# Sheet1.net
KiCad netlist of a schematic drawn in Altium Designer
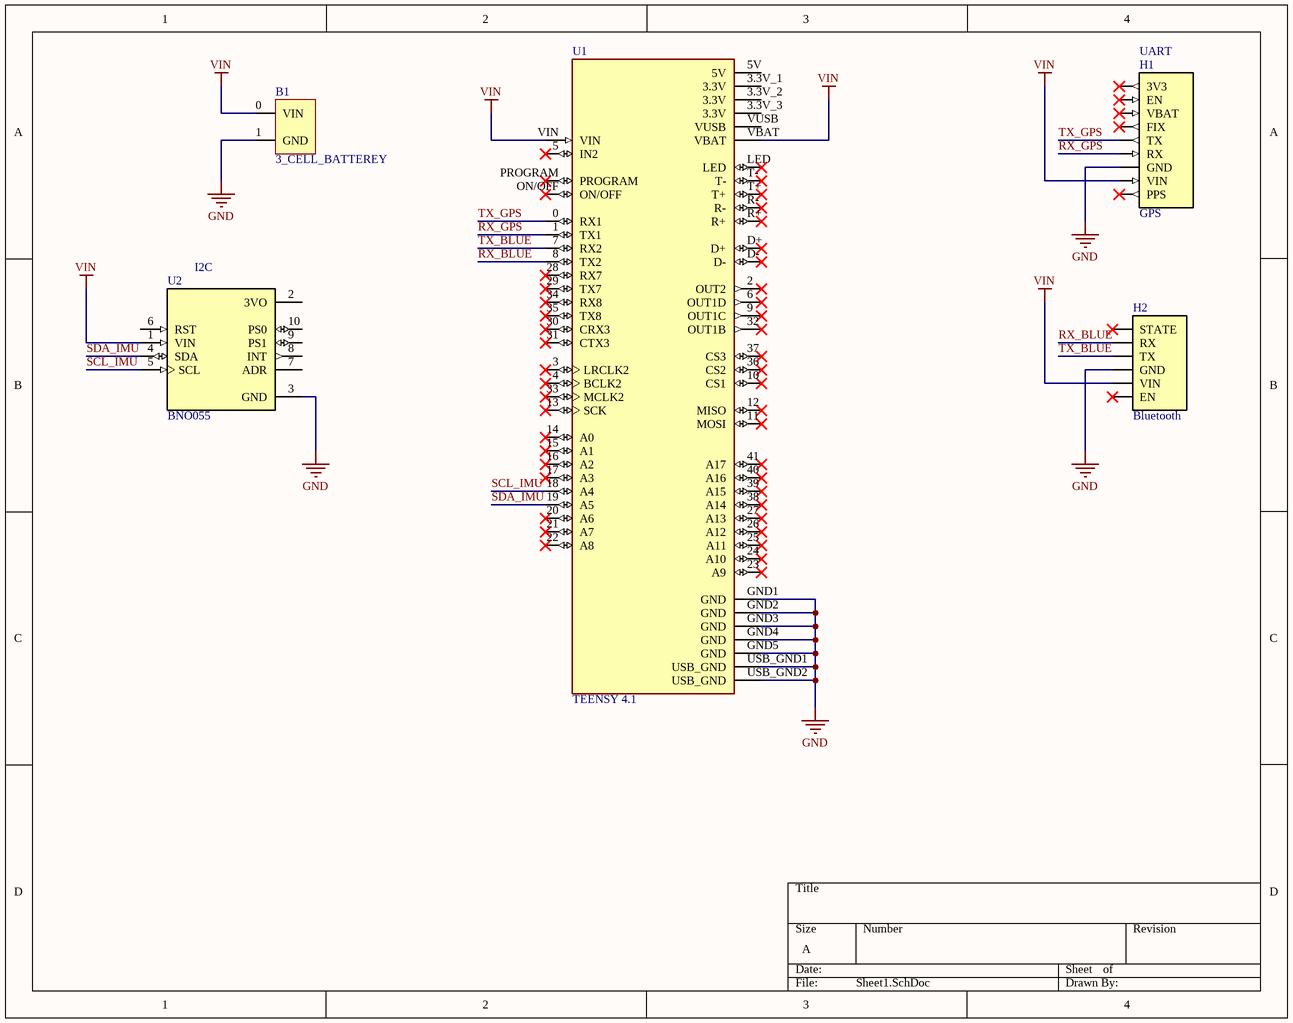
[diagram p0: Sheet1.SchDoc]

(export (version "E")
  (design (tool "Eeschema 10.0.6"))
  (components
    (comp (ref "B1")
      (value "3_CELL_BATTEREY")
      (footprint "3_CELL_BATTEREY")
      (libsource (lib "Schlib1") (part "3_CELL_BATTEREY"))
    )
    (comp (ref "H1") (value "GPS") (footprint "9X1_header") (libsource (lib "Schlib1") (part "9x1_header")))
    (comp (ref "H2")
      (value "Bluetooth")
      (footprint "61300611121")
      (libsource (lib "Schlib1") (part "Bluetooth"))
    )
    (comp (ref "U1")
      (value "TEENSY 4.1")
      (footprint "MODULE_DEV-16771")
      (description "RT1062 Teensy 4.1 series ARM® Cortex®-M7 MPU Embedded Evaluation Board")
      (fields (field (name "MF") "SparkFun Electronics") (field (name "MP") "DEV-16771"))
      (libsource (lib "Schlib1") (part "DEV-16771_1"))
    )
    (comp (ref "U2")
      (value "BNO055")
      (footprint "MODULE_2472")
      (description "Adafruit 9-DOF Absolute Orientation IMU Fusion Breakout - BNO055 ¦ Adafruit Industries 2472")
      (fields (field (name "MF") "Adafruit") (field (name "MP") "2472"))
      (libsource (lib "Schlib1") (part "2472"))
    )
  )
  (nets
    (net (code "1") (name "/RX_BLUE") (class "Default")
      (node (ref "H2") (pin "2") (pinfunction "RX_2") (pintype "passive"))
      (node (ref "U1") (pin "8") (pinfunction "TX2_8") (pintype "bidirectional"))
    )
    (net (code "2") (name "/RX_GPS") (class "Default")
      (node (ref "H1") (pin "5") (pinfunction "RX_5") (pintype "input"))
      (node (ref "U1") (pin "1") (pinfunction "TX1_1") (pintype "bidirectional"))
    )
    (net (code "3") (name "/SCL_IMU") (class "Default")
      (node (ref "U1") (pin "18") (pinfunction "A4_18") (pintype "bidirectional"))
      (node (ref "U2") (pin "5") (pinfunction "SCL_5") (pintype "input"))
    )
    (net (code "4") (name "/SDA_IMU") (class "Default")
      (node (ref "U1") (pin "19") (pinfunction "A5_19") (pintype "bidirectional"))
      (node (ref "U2") (pin "4") (pinfunction "SDA_4") (pintype "bidirectional"))
    )
    (net (code "5") (name "/TX_BLUE") (class "Default")
      (node (ref "H2") (pin "3") (pinfunction "TX_3") (pintype "passive"))
      (node (ref "U1") (pin "7") (pinfunction "RX2_7") (pintype "bidirectional"))
    )
    (net (code "6") (name "/TX_GPS") (class "Default")
      (node (ref "H1") (pin "4") (pinfunction "TX_4") (pintype "output"))
      (node (ref "U1") (pin "0") (pinfunction "RX1_0") (pintype "bidirectional"))
    )
    (net (code "7") (name "GND") (class "Default")
      (node (ref "B1") (pin "1") (pinfunction "GND_1") (pintype "passive"))
      (node (ref "H1") (pin "6") (pinfunction "GND_6") (pintype "passive"))
      (node (ref "H2") (pin "4") (pinfunction "GND_4") (pintype "passive"))
      (node (ref "U1") (pin "GND1") (pinfunction "GND_GND1") (pintype "power_in"))
      (node (ref "U1") (pin "GND2") (pinfunction "GND_GND2") (pintype "power_in"))
      (node (ref "U1") (pin "GND3") (pinfunction "GND_GND3") (pintype "power_in"))
      (node (ref "U1") (pin "GND4") (pinfunction "GND_GND4") (pintype "power_in"))
      (node (ref "U1") (pin "GND5") (pinfunction "GND_GND5") (pintype "power_in"))
      (node (ref "U1") (pin "USB_GND1") (pinfunction "USB_GND_USB_GND1") (pintype "power_in"))
      (node (ref "U1") (pin "USB_GND2") (pinfunction "USB_GND_USB_GND2") (pintype "power_in"))
      (node (ref "U2") (pin "3") (pinfunction "GND_3") (pintype "power_in"))
    )
    (net (code "8") (name "VIN") (class "Default")
      (node (ref "B1") (pin "0") (pinfunction "VIN_0") (pintype "passive"))
      (node (ref "H1") (pin "7") (pinfunction "VIN_7") (pintype "input"))
      (node (ref "H2") (pin "5") (pinfunction "VIN_5") (pintype "passive"))
      (node (ref "U1") (pin "VBAT") (pinfunction "VBAT_VBAT") (pintype "passive"))
      (node (ref "U1") (pin "VIN") (pinfunction "VIN_VIN") (pintype "input"))
      (node (ref "U2") (pin "1") (pinfunction "VIN_1") (pintype "input"))
    )
    (net (code "9") (name "unconnected-(H1-3V3-Pad0)") (class "Default")
      (node (ref "H1") (pin "0") (pinfunction "3V3_0") (pintype "output+no_connect"))
    )
    (net (code "10") (name "unconnected-(H1-EN-Pad1)") (class "Default")
      (node (ref "H1") (pin "1") (pinfunction "EN_1") (pintype "input+no_connect"))
    )
    (net (code "11") (name "unconnected-(H1-FIX-Pad3)") (class "Default")
      (node (ref "H1") (pin "3") (pinfunction "FIX_3") (pintype "output+no_connect"))
    )
    (net (code "12") (name "unconnected-(H1-PPS-Pad8)") (class "Default")
      (node (ref "H1") (pin "8") (pinfunction "PPS_8") (pintype "output+no_connect"))
    )
    (net (code "13") (name "unconnected-(H1-VBAT-Pad2)") (class "Default")
      (node (ref "H1") (pin "2") (pinfunction "VBAT_2") (pintype "input+no_connect"))
    )
    (net (code "14") (name "unconnected-(H2-EN-Pad6)") (class "Default")
      (node (ref "H2") (pin "6") (pinfunction "EN_6") (pintype "passive+no_connect"))
    )
    (net (code "15") (name "unconnected-(H2-STATE-Pad1)") (class "Default")
      (node (ref "H2") (pin "1") (pinfunction "STATE_1") (pintype "passive+no_connect"))
    )
    (net (code "16") (name "unconnected-(U1-3.3V-Pad3.3V_1)") (class "Default")
      (node (ref "U1") (pin "3.3V_1") (pinfunction "3.3V_3.3V_1") (pintype "power_in"))
    )
    (net (code "17") (name "unconnected-(U1-3.3V-Pad3.3V_2)") (class "Default")
      (node (ref "U1") (pin "3.3V_2") (pinfunction "3.3V_3.3V_2") (pintype "power_in"))
    )
    (net (code "18") (name "unconnected-(U1-3.3V-Pad3.3V_3)") (class "Default")
      (node (ref "U1") (pin "3.3V_3") (pinfunction "3.3V_3.3V_3") (pintype "power_in"))
    )
    (net (code "19") (name "unconnected-(U1-A0-Pad14)") (class "Default")
      (node (ref "U1") (pin "14") (pinfunction "A0_14") (pintype "bidirectional+no_connect"))
    )
    (net (code "20") (name "unconnected-(U1-A1-Pad15)") (class "Default")
      (node (ref "U1") (pin "15") (pinfunction "A1_15") (pintype "bidirectional+no_connect"))
    )
    (net (code "21") (name "unconnected-(U1-A2-Pad16)") (class "Default")
      (node (ref "U1") (pin "16") (pinfunction "A2_16") (pintype "bidirectional+no_connect"))
    )
    (net (code "22") (name "unconnected-(U1-A3-Pad17)") (class "Default")
      (node (ref "U1") (pin "17") (pinfunction "A3_17") (pintype "bidirectional+no_connect"))
    )
    (net (code "23") (name "unconnected-(U1-A6-Pad20)") (class "Default")
      (node (ref "U1") (pin "20") (pinfunction "A6_20") (pintype "bidirectional+no_connect"))
    )
    (net (code "24") (name "unconnected-(U1-A7-Pad21)") (class "Default")
      (node (ref "U1") (pin "21") (pinfunction "A7_21") (pintype "bidirectional+no_connect"))
    )
    (net (code "25") (name "unconnected-(U1-A8-Pad22)") (class "Default")
      (node (ref "U1") (pin "22") (pinfunction "A8_22") (pintype "bidirectional+no_connect"))
    )
    (net (code "26") (name "unconnected-(U1-A9-Pad23)") (class "Default")
      (node (ref "U1") (pin "23") (pinfunction "A9_23") (pintype "bidirectional+no_connect"))
    )
    (net (code "27") (name "unconnected-(U1-A10-Pad24)") (class "Default")
      (node (ref "U1") (pin "24") (pinfunction "A10_24") (pintype "bidirectional+no_connect"))
    )
    (net (code "28") (name "unconnected-(U1-A11-Pad25)") (class "Default")
      (node (ref "U1") (pin "25") (pinfunction "A11_25") (pintype "bidirectional+no_connect"))
    )
    (net (code "29") (name "unconnected-(U1-A12-Pad26)") (class "Default")
      (node (ref "U1") (pin "26") (pinfunction "A12_26") (pintype "bidirectional+no_connect"))
    )
    (net (code "30") (name "unconnected-(U1-A13-Pad27)") (class "Default")
      (node (ref "U1") (pin "27") (pinfunction "A13_27") (pintype "bidirectional+no_connect"))
    )
    (net (code "31") (name "unconnected-(U1-A14-Pad38)") (class "Default")
      (node (ref "U1") (pin "38") (pinfunction "A14_38") (pintype "bidirectional+no_connect"))
    )
    (net (code "32") (name "unconnected-(U1-A15-Pad39)") (class "Default")
      (node (ref "U1") (pin "39") (pinfunction "A15_39") (pintype "bidirectional+no_connect"))
    )
    (net (code "33") (name "unconnected-(U1-A16-Pad40)") (class "Default")
      (node (ref "U1") (pin "40") (pinfunction "A16_40") (pintype "bidirectional+no_connect"))
    )
    (net (code "34") (name "unconnected-(U1-A17-Pad41)") (class "Default")
      (node (ref "U1") (pin "41") (pinfunction "A17_41") (pintype "bidirectional+no_connect"))
    )
    (net (code "35") (name "unconnected-(U1-BCLK2-Pad4)") (class "Default")
      (node (ref "U1") (pin "4") (pinfunction "BCLK2_4") (pintype "bidirectional+no_connect"))
    )
    (net (code "36") (name "unconnected-(U1-CRX3-Pad30)") (class "Default")
      (node (ref "U1") (pin "30") (pinfunction "CRX3_30") (pintype "bidirectional+no_connect"))
    )
    (net (code "37") (name "unconnected-(U1-CS1-Pad10)") (class "Default")
      (node (ref "U1") (pin "10") (pinfunction "CS1_10") (pintype "bidirectional+no_connect"))
    )
    (net (code "38") (name "unconnected-(U1-CS2-Pad36)") (class "Default")
      (node (ref "U1") (pin "36") (pinfunction "CS2_36") (pintype "bidirectional+no_connect"))
    )
    (net (code "39") (name "unconnected-(U1-CS3-Pad37)") (class "Default")
      (node (ref "U1") (pin "37") (pinfunction "CS3_37") (pintype "bidirectional+no_connect"))
    )
    (net (code "40") (name "unconnected-(U1-CTX3-Pad31)") (class "Default")
      (node (ref "U1") (pin "31") (pinfunction "CTX3_31") (pintype "bidirectional+no_connect"))
    )
    (net (code "41") (name "unconnected-(U1-IN2-Pad5)") (class "Default")
      (node (ref "U1") (pin "5") (pinfunction "IN2_5") (pintype "bidirectional+no_connect"))
    )
    (net (code "42") (name "unconnected-(U1-LRCLK2-Pad3)") (class "Default")
      (node (ref "U1") (pin "3") (pinfunction "LRCLK2_3") (pintype "bidirectional+no_connect"))
    )
    (net (code "43") (name "unconnected-(U1-MCLK2-Pad33)") (class "Default")
      (node (ref "U1") (pin "33") (pinfunction "MCLK2_33") (pintype "bidirectional+no_connect"))
    )
    (net (code "44") (name "unconnected-(U1-MISO-Pad12)") (class "Default")
      (node (ref "U1") (pin "12") (pinfunction "MISO_12") (pintype "bidirectional+no_connect"))
    )
    (net (code "45") (name "unconnected-(U1-MOSI-Pad11)") (class "Default")
      (node (ref "U1") (pin "11") (pinfunction "MOSI_11") (pintype "bidirectional+no_connect"))
    )
    (net (code "46") (name "unconnected-(U1-OUT1B-Pad32)") (class "Default")
      (node (ref "U1") (pin "32") (pinfunction "OUT1B_32") (pintype "output+no_connect"))
    )
    (net (code "47") (name "unconnected-(U1-OUT1C-Pad9)") (class "Default")
      (node (ref "U1") (pin "9") (pinfunction "OUT1C_9") (pintype "output+no_connect"))
    )
    (net (code "48") (name "unconnected-(U1-OUT1D-Pad6)") (class "Default")
      (node (ref "U1") (pin "6") (pinfunction "OUT1D_6") (pintype "output+no_connect"))
    )
    (net (code "49") (name "unconnected-(U1-OUT2-Pad2)") (class "Default")
      (node (ref "U1") (pin "2") (pinfunction "OUT2_2") (pintype "output+no_connect"))
    )
    (net (code "50") (name "unconnected-(U1-Pad5V)") (class "Default")
      (node (ref "U1") (pin "5V") (pinfunction "5V_5V") (pintype "power_in"))
    )
    (net (code "51") (name "unconnected-(U1-PadD+)") (class "Default")
      (node (ref "U1") (pin "D+") (pinfunction "D+_D+") (pintype "bidirectional+no_connect"))
    )
    (net (code "52") (name "unconnected-(U1-PadD-)") (class "Default")
      (node (ref "U1") (pin "D-") (pinfunction "D-_D-") (pintype "bidirectional+no_connect"))
    )
    (net (code "53") (name "unconnected-(U1-PadLED)") (class "Default")
      (node (ref "U1") (pin "LED") (pinfunction "LED_LED") (pintype "bidirectional+no_connect"))
    )
    (net (code "54") (name "unconnected-(U1-PadON{slash}OFF)") (class "Default")
      (node (ref "U1") (pin "ON/OFF") (pinfunction "ON/OFF_ON/OFF") (pintype "bidirectional+no_connect"))
    )
    (net (code "55") (name "unconnected-(U1-PadPROGRAM)") (class "Default")
      (node (ref "U1") (pin "PROGRAM") (pinfunction "PROGRAM_PROGRAM") (pintype "bidirectional+no_connect"))
    )
    (net (code "56") (name "unconnected-(U1-PadR+)") (class "Default")
      (node (ref "U1") (pin "R+") (pinfunction "R+_R+") (pintype "bidirectional+no_connect"))
    )
    (net (code "57") (name "unconnected-(U1-PadR-)") (class "Default")
      (node (ref "U1") (pin "R-") (pinfunction "R-_R-") (pintype "bidirectional+no_connect"))
    )
    (net (code "58") (name "unconnected-(U1-PadT+)") (class "Default")
      (node (ref "U1") (pin "T+") (pinfunction "T+_T+") (pintype "bidirectional+no_connect"))
    )
    (net (code "59") (name "unconnected-(U1-PadT-)") (class "Default")
      (node (ref "U1") (pin "T-") (pinfunction "T-_T-") (pintype "bidirectional+no_connect"))
    )
    (net (code "60") (name "unconnected-(U1-PadVUSB)") (class "Default")
      (node (ref "U1") (pin "VUSB") (pinfunction "VUSB_VUSB") (pintype "passive"))
    )
    (net (code "61") (name "unconnected-(U1-RX7-Pad28)") (class "Default")
      (node (ref "U1") (pin "28") (pinfunction "RX7_28") (pintype "bidirectional+no_connect"))
    )
    (net (code "62") (name "unconnected-(U1-RX8-Pad34)") (class "Default")
      (node (ref "U1") (pin "34") (pinfunction "RX8_34") (pintype "bidirectional+no_connect"))
    )
    (net (code "63") (name "unconnected-(U1-SCK-Pad13)") (class "Default")
      (node (ref "U1") (pin "13") (pinfunction "SCK_13") (pintype "bidirectional+no_connect"))
    )
    (net (code "64") (name "unconnected-(U1-TX7-Pad29)") (class "Default")
      (node (ref "U1") (pin "29") (pinfunction "TX7_29") (pintype "bidirectional+no_connect"))
    )
    (net (code "65") (name "unconnected-(U1-TX8-Pad35)") (class "Default")
      (node (ref "U1") (pin "35") (pinfunction "TX8_35") (pintype "bidirectional+no_connect"))
    )
    (net (code "66") (name "unconnected-(U2-3VO-Pad2)") (class "Default")
      (node (ref "U2") (pin "2") (pinfunction "3VO_2") (pintype "power_in"))
    )
    (net (code "67") (name "unconnected-(U2-ADR-Pad7)") (class "Default")
      (node (ref "U2") (pin "7") (pinfunction "ADR_7") (pintype "passive"))
    )
    (net (code "68") (name "unconnected-(U2-INT-Pad8)") (class "Default")
      (node (ref "U2") (pin "8") (pinfunction "INT_8") (pintype "output"))
    )
    (net (code "69") (name "unconnected-(U2-PS0-Pad10)") (class "Default")
      (node (ref "U2") (pin "10") (pinfunction "PS0_10") (pintype "bidirectional"))
    )
    (net (code "70") (name "unconnected-(U2-PS1-Pad9)") (class "Default")
      (node (ref "U2") (pin "9") (pinfunction "PS1_9") (pintype "bidirectional"))
    )
    (net (code "71") (name "unconnected-(U2-RST-Pad6)") (class "Default")
      (node (ref "U2") (pin "6") (pinfunction "RST_6") (pintype "input"))
    )
  )
)
